# SCH_USB-Hub_2025-02-03.net
KiCad netlist of a schematic drawn in EasyEDA
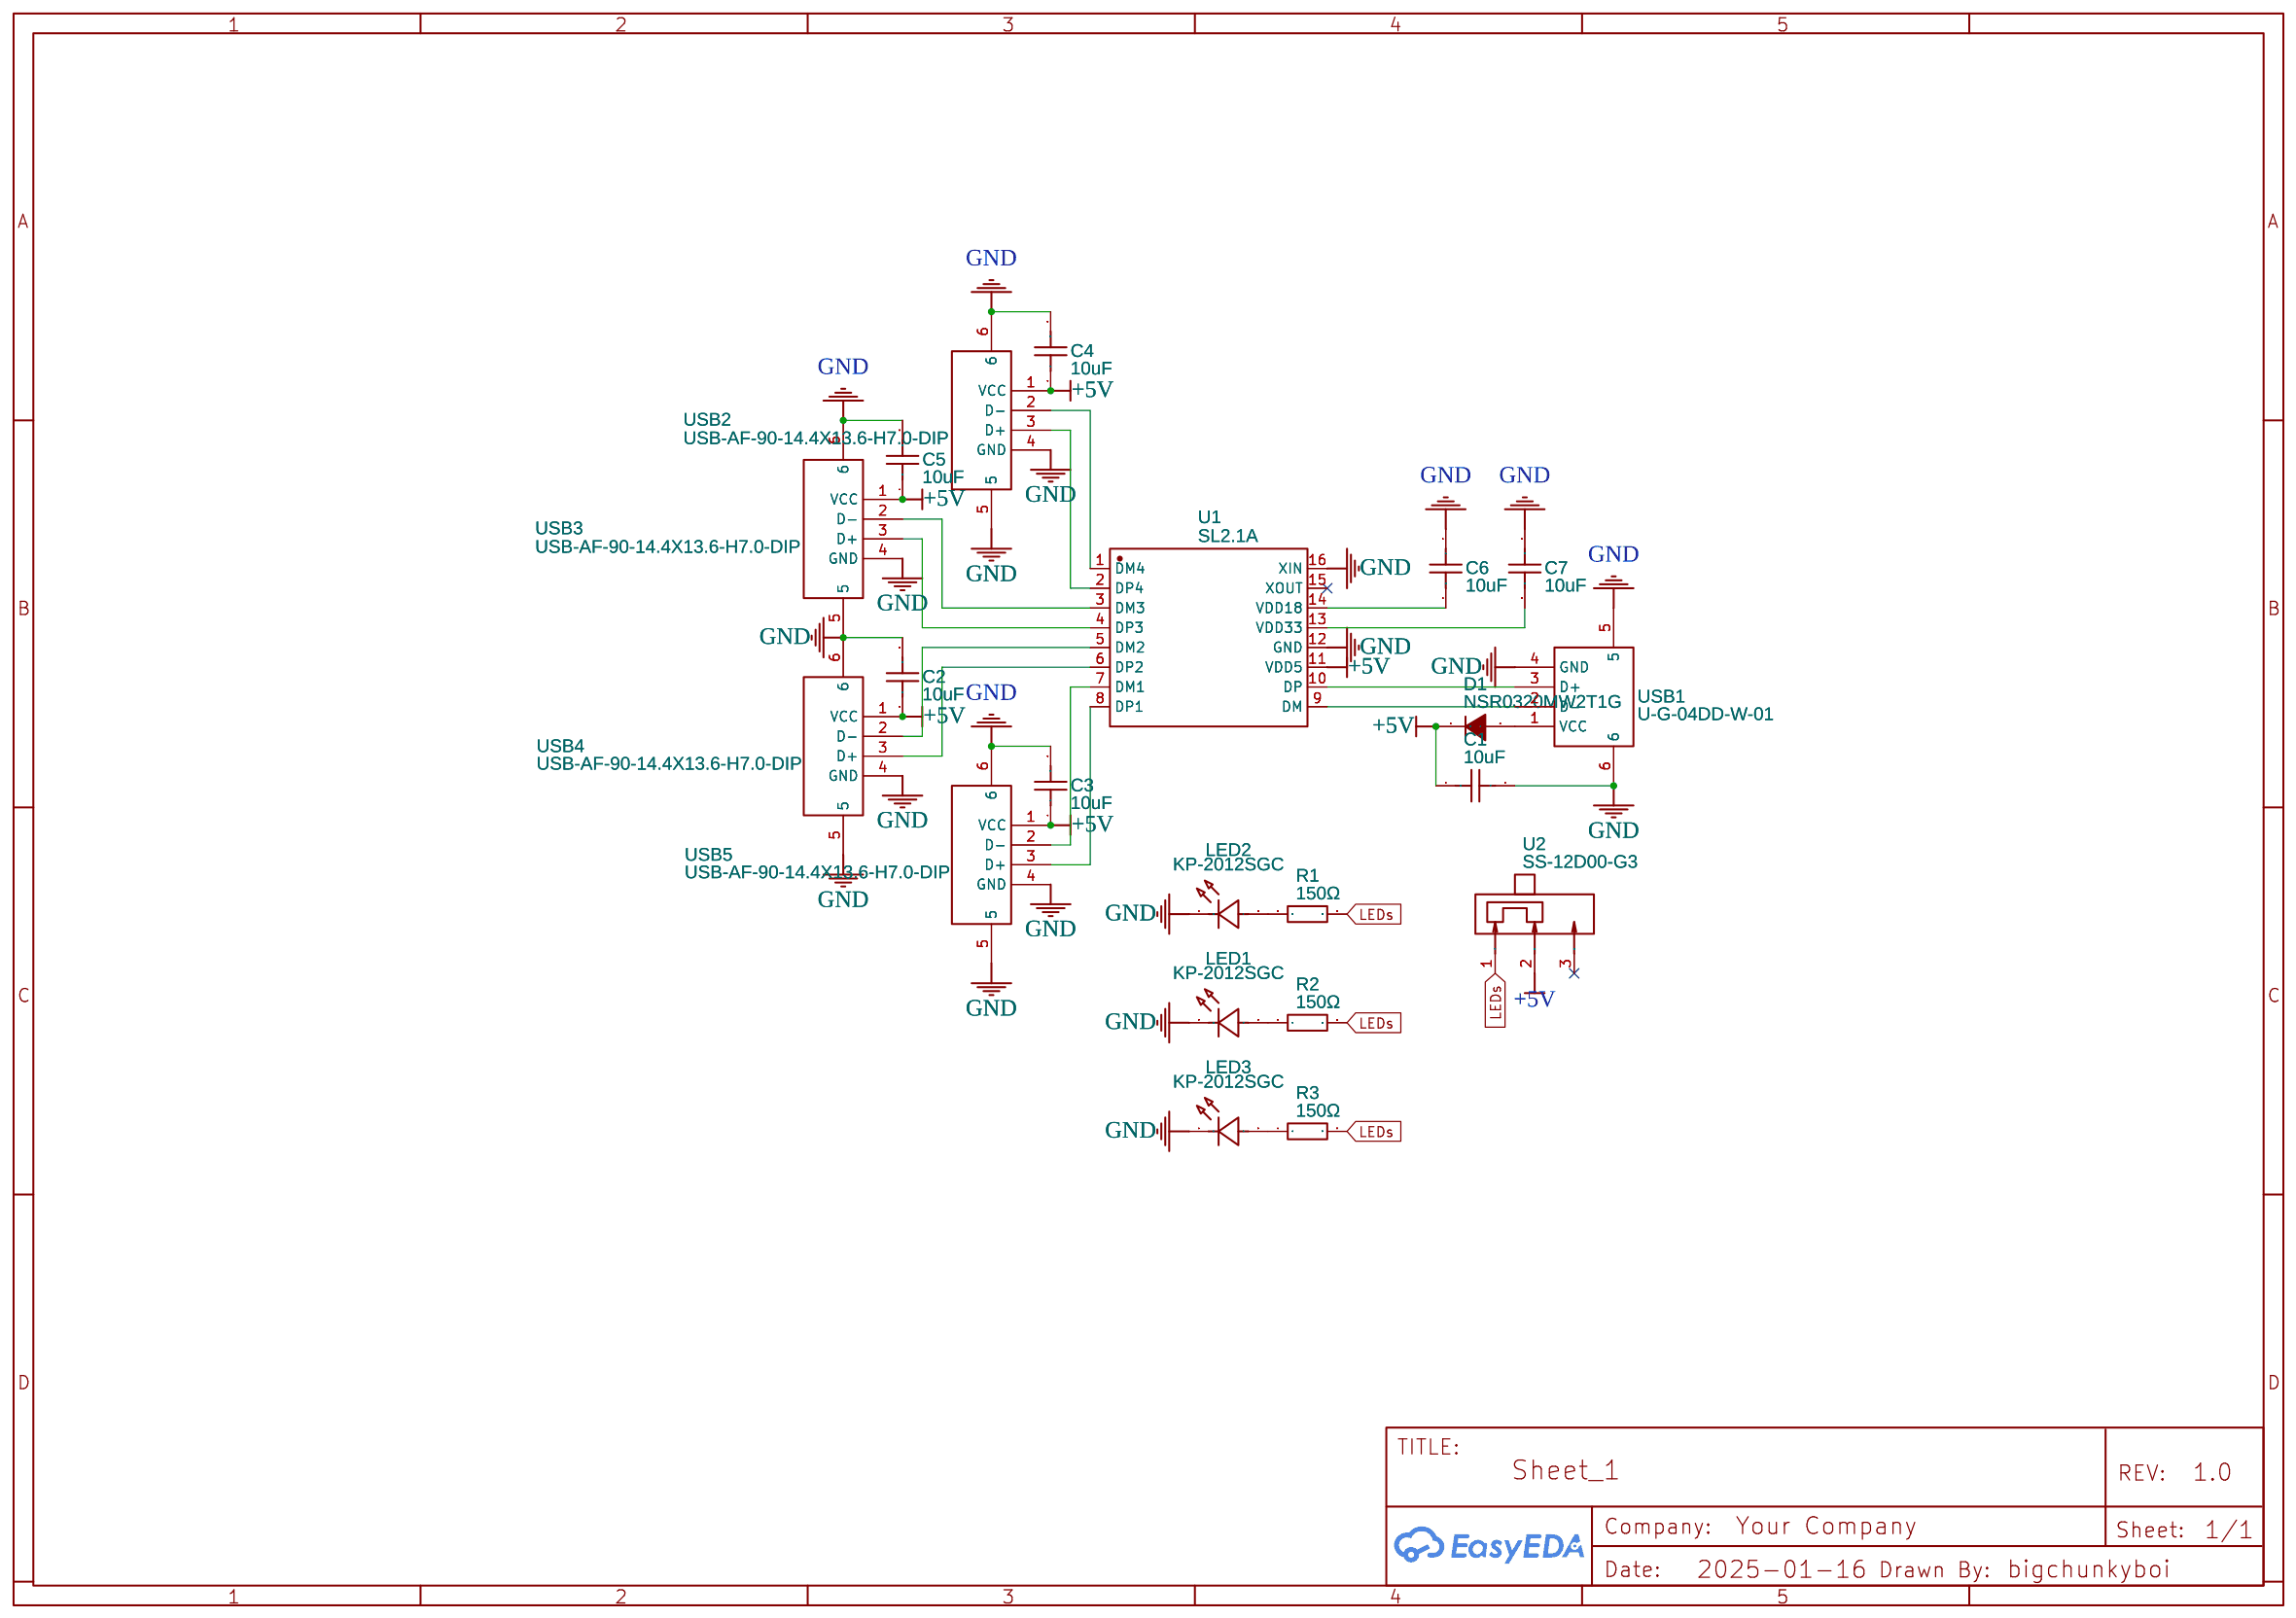
[diagram p0: schematic sheet]

(export (version "E")
  (design (tool "Eeschema 10.0.6"))
  (components
    (comp (ref "C1")
      (value "10uF")
      (fields
        (field (name "Manufacturer Part") "CL10A106KP8NNNC")
        (field (name "Manufacturer") "SAMSUNG(三星)")
      )
      (libsource (lib "") (part "CL10A106KP8NNNC_2"))
    )
    (comp (ref "C2")
      (value "10uF")
      (fields
        (field (name "Manufacturer Part") "CL10A106KP8NNNC")
        (field (name "Manufacturer") "SAMSUNG(三星)")
      )
      (libsource (lib "") (part "CL10A106KP8NNNC"))
    )
    (comp (ref "C3")
      (value "10uF")
      (fields
        (field (name "Manufacturer Part") "CL10A106KP8NNNC")
        (field (name "Manufacturer") "SAMSUNG(三星)")
      )
      (libsource (lib "") (part "CL10A106KP8NNNC"))
    )
    (comp (ref "C4")
      (value "10uF")
      (fields
        (field (name "Manufacturer Part") "CL10A106KP8NNNC")
        (field (name "Manufacturer") "SAMSUNG(三星)")
      )
      (libsource (lib "") (part "CL10A106KP8NNNC"))
    )
    (comp (ref "C5")
      (value "10uF")
      (fields
        (field (name "Manufacturer Part") "CL10A106KP8NNNC")
        (field (name "Manufacturer") "SAMSUNG(三星)")
      )
      (libsource (lib "") (part "CL10A106KP8NNNC"))
    )
    (comp (ref "C6")
      (value "10uF")
      (fields
        (field (name "Manufacturer Part") "CL10A106KP8NNNC")
        (field (name "Manufacturer") "SAMSUNG(三星)")
      )
      (libsource (lib "") (part "CL10A106KP8NNNC_1"))
    )
    (comp (ref "C7")
      (value "10uF")
      (fields
        (field (name "Manufacturer Part") "CL10A106KP8NNNC")
        (field (name "Manufacturer") "SAMSUNG(三星)")
      )
      (libsource (lib "") (part "CL10A106KP8NNNC_1"))
    )
    (comp (ref "D1")
      (value "NSR0320MW2T1G")
      (fields (field (name "Manufacturer") "onsemi(安森美)"))
      (libsource (lib "") (part "NSR0320MW2T1G"))
    )
    (comp (ref "LED1")
      (value "KP-2012SGC")
      (fields (field (name "Manufacturer") "Kingbright"))
      (libsource (lib "") (part "KP-2012SGC"))
    )
    (comp (ref "LED2")
      (value "KP-2012SGC")
      (fields (field (name "Manufacturer") "Kingbright"))
      (libsource (lib "") (part "KP-2012SGC"))
    )
    (comp (ref "LED3")
      (value "KP-2012SGC")
      (fields (field (name "Manufacturer") "Kingbright"))
      (libsource (lib "") (part "KP-2012SGC"))
    )
    (comp (ref "R1")
      (value "150Ω")
      (fields (field (name "Manufacturer Part") "RC0603FR-07150RL") (field (name "Manufacturer") "YAGEO(国巨)"))
      (libsource (lib "") (part "RC0603FR-07150RL"))
    )
    (comp (ref "R2")
      (value "150Ω")
      (fields (field (name "Manufacturer Part") "RC0603FR-07150RL") (field (name "Manufacturer") "YAGEO(国巨)"))
      (libsource (lib "") (part "RC0603FR-07150RL"))
    )
    (comp (ref "R3")
      (value "150Ω")
      (fields (field (name "Manufacturer Part") "RC0603FR-07150RL") (field (name "Manufacturer") "YAGEO(国巨)"))
      (libsource (lib "") (part "RC0603FR-07150RL"))
    )
    (comp (ref "U1")
      (value "SL2.1A")
      (fields (field (name "Manufacturer") "CoreChips(和芯润德)"))
      (libsource (lib "") (part "SL2.1A"))
    )
    (comp (ref "U2")
      (value "SS-12D00-G3")
      (fields (field (name "Manufacturer") "SOFNG(硕方)"))
      (libsource (lib "") (part "SS-12D00-G3"))
    )
    (comp (ref "USB1")
      (value "U-G-04DD-W-01")
      (fields (field (name "Manufacturer Part") "U-G-O4DD-W-1") (field (name "Manufacturer") "韩国韩荣"))
      (libsource (lib "") (part "U-G-04DD-W-01"))
    )
    (comp (ref "USB2")
      (value "USB-AF-90-14.4X13.6-H7.0-DIP")
      (fields (field (name "Manufacturer Part") "903-131A1011D10100") (field (name "Manufacturer") "精拓金"))
      (libsource (lib "") (part "USB-AF-90-14.4X13.6-H7.0-DIP"))
    )
    (comp (ref "USB3")
      (value "USB-AF-90-14.4X13.6-H7.0-DIP")
      (fields (field (name "Manufacturer Part") "903-131A1011D10100") (field (name "Manufacturer") "精拓金"))
      (libsource (lib "") (part "USB-AF-90-14.4X13.6-H7.0-DIP"))
    )
    (comp (ref "USB4")
      (value "USB-AF-90-14.4X13.6-H7.0-DIP")
      (fields (field (name "Manufacturer Part") "903-131A1011D10100") (field (name "Manufacturer") "精拓金"))
      (libsource (lib "") (part "USB-AF-90-14.4X13.6-H7.0-DIP"))
    )
    (comp (ref "USB5")
      (value "USB-AF-90-14.4X13.6-H7.0-DIP")
      (fields (field (name "Manufacturer Part") "903-131A1011D10100") (field (name "Manufacturer") "精拓金"))
      (libsource (lib "") (part "USB-AF-90-14.4X13.6-H7.0-DIP"))
    )
  )
  (nets
    (net (code "1") (name "+5V") (class "Default")
      (node (ref "C1") (pin "1") (pinfunction "1_1") (pintype "unspecified"))
      (node (ref "C2") (pin "1") (pinfunction "1_1") (pintype "unspecified"))
      (node (ref "C3") (pin "1") (pinfunction "1_1") (pintype "unspecified"))
      (node (ref "C4") (pin "1") (pinfunction "1_1") (pintype "unspecified"))
      (node (ref "C5") (pin "1") (pinfunction "1_1") (pintype "unspecified"))
      (node (ref "D1") (pin "1") (pinfunction "C_1") (pintype "unspecified"))
      (node (ref "U1") (pin "11") (pinfunction "VDD5_11") (pintype "unspecified"))
      (node (ref "U2") (pin "2") (pinfunction "2_2") (pintype "unspecified"))
      (node (ref "USB2") (pin "1") (pinfunction "VCC_1") (pintype "unspecified"))
      (node (ref "USB3") (pin "1") (pinfunction "VCC_1") (pintype "unspecified"))
      (node (ref "USB4") (pin "1") (pinfunction "VCC_1") (pintype "unspecified"))
      (node (ref "USB5") (pin "1") (pinfunction "VCC_1") (pintype "unspecified"))
    )
    (net (code "2") (name "GND") (class "Default")
      (node (ref "C1") (pin "2") (pinfunction "2_2") (pintype "unspecified"))
      (node (ref "C2") (pin "2") (pinfunction "2_2") (pintype "unspecified"))
      (node (ref "C3") (pin "2") (pinfunction "2_2") (pintype "unspecified"))
      (node (ref "C4") (pin "2") (pinfunction "2_2") (pintype "unspecified"))
      (node (ref "C5") (pin "2") (pinfunction "2_2") (pintype "unspecified"))
      (node (ref "C6") (pin "1") (pinfunction "1_1") (pintype "unspecified"))
      (node (ref "C7") (pin "1") (pinfunction "1_1") (pintype "unspecified"))
      (node (ref "LED1") (pin "1") (pinfunction "K_1") (pintype "unspecified"))
      (node (ref "LED2") (pin "1") (pinfunction "K_1") (pintype "unspecified"))
      (node (ref "LED3") (pin "1") (pinfunction "K_1") (pintype "unspecified"))
      (node (ref "U1") (pin "12") (pinfunction "GND_12") (pintype "unspecified"))
      (node (ref "U1") (pin "16") (pinfunction "XIN_16") (pintype "unspecified"))
      (node (ref "USB1") (pin "4") (pinfunction "GND_4") (pintype "unspecified"))
      (node (ref "USB1") (pin "5") (pinfunction "5_5") (pintype "unspecified"))
      (node (ref "USB1") (pin "6") (pinfunction "6_6") (pintype "unspecified"))
      (node (ref "USB2") (pin "4") (pinfunction "GND_4") (pintype "unspecified"))
      (node (ref "USB2") (pin "5") (pinfunction "5_5") (pintype "unspecified"))
      (node (ref "USB2") (pin "6") (pinfunction "6_6") (pintype "unspecified"))
      (node (ref "USB3") (pin "4") (pinfunction "GND_4") (pintype "unspecified"))
      (node (ref "USB3") (pin "5") (pinfunction "5_5") (pintype "unspecified"))
      (node (ref "USB3") (pin "6") (pinfunction "6_6") (pintype "unspecified"))
      (node (ref "USB4") (pin "4") (pinfunction "GND_4") (pintype "unspecified"))
      (node (ref "USB4") (pin "5") (pinfunction "5_5") (pintype "unspecified"))
      (node (ref "USB4") (pin "6") (pinfunction "6_6") (pintype "unspecified"))
      (node (ref "USB5") (pin "4") (pinfunction "GND_4") (pintype "unspecified"))
      (node (ref "USB5") (pin "5") (pinfunction "5_5") (pintype "unspecified"))
      (node (ref "USB5") (pin "6") (pinfunction "6_6") (pintype "unspecified"))
    )
    (net (code "3") (name "LEDs") (class "Default")
      (node (ref "R1") (pin "2") (pinfunction "2_2") (pintype "input"))
      (node (ref "R2") (pin "2") (pinfunction "2_2") (pintype "input"))
      (node (ref "R3") (pin "2") (pinfunction "2_2") (pintype "input"))
      (node (ref "U2") (pin "1") (pinfunction "1_1") (pintype "unspecified"))
    )
    (net (code "4") (name "Net-(D1-A)") (class "Default")
      (node (ref "D1") (pin "2") (pinfunction "A_2") (pintype "unspecified"))
      (node (ref "USB1") (pin "1") (pinfunction "VCC_1") (pintype "unspecified"))
    )
    (net (code "5") (name "Net-(LED1-A)") (class "Default")
      (node (ref "LED1") (pin "2") (pinfunction "A_2") (pintype "unspecified"))
      (node (ref "R2") (pin "1") (pinfunction "1_1") (pintype "input"))
    )
    (net (code "6") (name "Net-(LED2-A)") (class "Default")
      (node (ref "LED2") (pin "2") (pinfunction "A_2") (pintype "unspecified"))
      (node (ref "R1") (pin "1") (pinfunction "1_1") (pintype "input"))
    )
    (net (code "7") (name "Net-(LED3-A)") (class "Default")
      (node (ref "LED3") (pin "2") (pinfunction "A_2") (pintype "unspecified"))
      (node (ref "R3") (pin "1") (pinfunction "1_1") (pintype "input"))
    )
    (net (code "8") (name "Net-(U1-DM)") (class "Default")
      (node (ref "U1") (pin "9") (pinfunction "DM_9") (pintype "unspecified"))
      (node (ref "USB1") (pin "2") (pinfunction "D-_2") (pintype "unspecified"))
    )
    (net (code "9") (name "Net-(U1-DM1)") (class "Default")
      (node (ref "U1") (pin "7") (pinfunction "DM1_7") (pintype "unspecified"))
      (node (ref "USB5") (pin "2") (pinfunction "D-_2") (pintype "unspecified"))
    )
    (net (code "10") (name "Net-(U1-DM2)") (class "Default")
      (node (ref "U1") (pin "5") (pinfunction "DM2_5") (pintype "unspecified"))
      (node (ref "USB4") (pin "2") (pinfunction "D-_2") (pintype "unspecified"))
    )
    (net (code "11") (name "Net-(U1-DM3)") (class "Default")
      (node (ref "U1") (pin "3") (pinfunction "DM3_3") (pintype "unspecified"))
      (node (ref "USB3") (pin "2") (pinfunction "D-_2") (pintype "unspecified"))
    )
    (net (code "12") (name "Net-(U1-DM4)") (class "Default")
      (node (ref "U1") (pin "1") (pinfunction "DM4_1") (pintype "unspecified"))
      (node (ref "USB2") (pin "2") (pinfunction "D-_2") (pintype "unspecified"))
    )
    (net (code "13") (name "Net-(U1-DP)") (class "Default")
      (node (ref "U1") (pin "10") (pinfunction "DP_10") (pintype "unspecified"))
      (node (ref "USB1") (pin "3") (pinfunction "D+_3") (pintype "unspecified"))
    )
    (net (code "14") (name "Net-(U1-DP1)") (class "Default")
      (node (ref "U1") (pin "8") (pinfunction "DP1_8") (pintype "unspecified"))
      (node (ref "USB5") (pin "3") (pinfunction "D+_3") (pintype "unspecified"))
    )
    (net (code "15") (name "Net-(U1-DP2)") (class "Default")
      (node (ref "U1") (pin "6") (pinfunction "DP2_6") (pintype "unspecified"))
      (node (ref "USB4") (pin "3") (pinfunction "D+_3") (pintype "unspecified"))
    )
    (net (code "16") (name "Net-(U1-DP3)") (class "Default")
      (node (ref "U1") (pin "4") (pinfunction "DP3_4") (pintype "unspecified"))
      (node (ref "USB3") (pin "3") (pinfunction "D+_3") (pintype "unspecified"))
    )
    (net (code "17") (name "Net-(U1-DP4)") (class "Default")
      (node (ref "U1") (pin "2") (pinfunction "DP4_2") (pintype "unspecified"))
      (node (ref "USB2") (pin "3") (pinfunction "D+_3") (pintype "unspecified"))
    )
    (net (code "18") (name "Net-(U1-VDD18)") (class "Default")
      (node (ref "C6") (pin "2") (pinfunction "2_2") (pintype "unspecified"))
      (node (ref "U1") (pin "14") (pinfunction "VDD18_14") (pintype "unspecified"))
    )
    (net (code "19") (name "Net-(U1-VDD33)") (class "Default")
      (node (ref "C7") (pin "2") (pinfunction "2_2") (pintype "unspecified"))
      (node (ref "U1") (pin "13") (pinfunction "VDD33_13") (pintype "unspecified"))
    )
    (net (code "20") (name "unconnected-(U1-XOUT-Pad15)") (class "Default")
      (node (ref "U1") (pin "15") (pinfunction "XOUT_15") (pintype "unspecified+no_connect"))
    )
    (net (code "21") (name "unconnected-(U2-Pad3)") (class "Default")
      (node (ref "U2") (pin "3") (pinfunction "3_3") (pintype "unspecified+no_connect"))
    )
  )
)
